# Crutch_Light.net
KiCad netlist of a schematic drawn in EAGLE
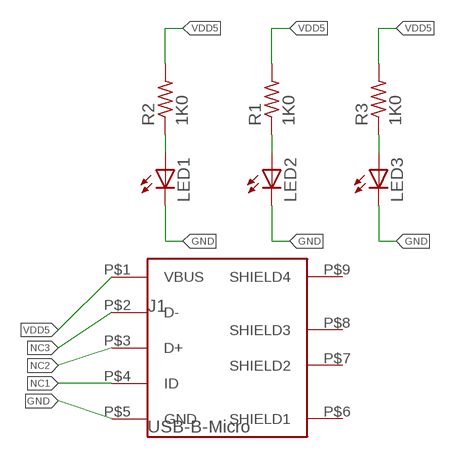
[diagram p0: schematic, sheet 1]

(export (version "E")
  (design (tool "Eeschema 10.0.6"))
  (components
    (comp (ref "J1")
      (value "USB-B-Micro")
      (footprint "eagle-import:USB_MICRO-B")
      (fields (field (name "PARTNO") "10118192-0002LF"))
      (libsource (lib "eagle-import") (part "USB_MICRO-B"))
    )
    (comp (ref "LED1")
      (value "Green")
      (footprint "eagle-import:0805")
      (fields (field (name "PARTNO") "LG R971-KN-1"))
      (libsource (lib "eagle-import") (part "LED_0805_GREEN"))
    )
    (comp (ref "LED2")
      (value "Green")
      (footprint "eagle-import:0805")
      (fields (field (name "PARTNO") "LG R971-KN-1"))
      (libsource (lib "eagle-import") (part "LED_0805_GREEN"))
    )
    (comp (ref "LED3")
      (value "Green")
      (footprint "eagle-import:0805")
      (fields (field (name "PARTNO") "LG R971-KN-1"))
      (libsource (lib "eagle-import") (part "LED_0805_GREEN"))
    )
    (comp (ref "R1")
      (value "1K0")
      (footprint "eagle-import:0402")
      (fields (field (name "PARTNO") "CRG0402J1K0"))
      (libsource (lib "eagle-import") (part "R_0402_1K0"))
    )
    (comp (ref "R2")
      (value "1K0")
      (footprint "eagle-import:0402")
      (fields (field (name "PARTNO") "CRG0402J1K0"))
      (libsource (lib "eagle-import") (part "R_0402_1K0"))
    )
    (comp (ref "R3")
      (value "1K0")
      (footprint "eagle-import:0402")
      (fields (field (name "PARTNO") "CRG0402J1K0"))
      (libsource (lib "eagle-import") (part "R_0402_1K0"))
    )
  )
  (nets
    (net (code "1") (name "GND") (class "Default")
      (node (ref "J1") (pin "P$5") (pinfunction "GND_P$5") (pintype "bidirectional"))
      (node (ref "LED1") (pin "2") (pinfunction "C_2") (pintype "passive"))
      (node (ref "LED2") (pin "2") (pinfunction "C_2") (pintype "passive"))
      (node (ref "LED3") (pin "2") (pinfunction "C_2") (pintype "passive"))
    )
    (net (code "2") (name "NC1") (class "Default")
      (node (ref "J1") (pin "P$4") (pinfunction "ID_P$4") (pintype "bidirectional"))
    )
    (net (code "3") (name "NC2") (class "Default")
      (node (ref "J1") (pin "P$3") (pinfunction "D+_P$3") (pintype "bidirectional"))
    )
    (net (code "4") (name "NC3") (class "Default")
      (node (ref "J1") (pin "P$2") (pinfunction "D-_P$2") (pintype "bidirectional"))
    )
    (net (code "5") (name "Net-(LED1-A)") (class "Default")
      (node (ref "LED1") (pin "1") (pinfunction "A_1") (pintype "passive"))
      (node (ref "R2") (pin "P$1") (pinfunction "1_P$1") (pintype "passive"))
    )
    (net (code "6") (name "Net-(LED2-A)") (class "Default")
      (node (ref "LED2") (pin "1") (pinfunction "A_1") (pintype "passive"))
      (node (ref "R1") (pin "P$1") (pinfunction "1_P$1") (pintype "passive"))
    )
    (net (code "7") (name "Net-(LED3-A)") (class "Default")
      (node (ref "LED3") (pin "1") (pinfunction "A_1") (pintype "passive"))
      (node (ref "R3") (pin "P$1") (pinfunction "1_P$1") (pintype "passive"))
    )
    (net (code "8") (name "VDD5") (class "Default")
      (node (ref "J1") (pin "P$1") (pinfunction "VBUS_P$1") (pintype "bidirectional"))
      (node (ref "R1") (pin "P$2") (pinfunction "2_P$2") (pintype "passive"))
      (node (ref "R2") (pin "P$2") (pinfunction "2_P$2") (pintype "passive"))
      (node (ref "R3") (pin "P$2") (pinfunction "2_P$2") (pintype "passive"))
    )
    (net (code "9") (name "unconnected-(J1-SHIELD1-PadP$6)") (class "Default")
      (node (ref "J1") (pin "P$6") (pinfunction "SHIELD1_P$6") (pintype "bidirectional"))
    )
    (net (code "10") (name "unconnected-(J1-SHIELD2-PadP$7)") (class "Default")
      (node (ref "J1") (pin "P$7") (pinfunction "SHIELD2_P$7") (pintype "bidirectional"))
    )
    (net (code "11") (name "unconnected-(J1-SHIELD3-PadP$8)") (class "Default")
      (node (ref "J1") (pin "P$8") (pinfunction "SHIELD3_P$8") (pintype "bidirectional"))
    )
    (net (code "12") (name "unconnected-(J1-SHIELD4-PadP$9)") (class "Default")
      (node (ref "J1") (pin "P$9") (pinfunction "SHIELD4_P$9") (pintype "bidirectional"))
    )
  )
)
